# UART_Comm_Isolation.net
KiCad netlist of a schematic drawn in Altium Designer
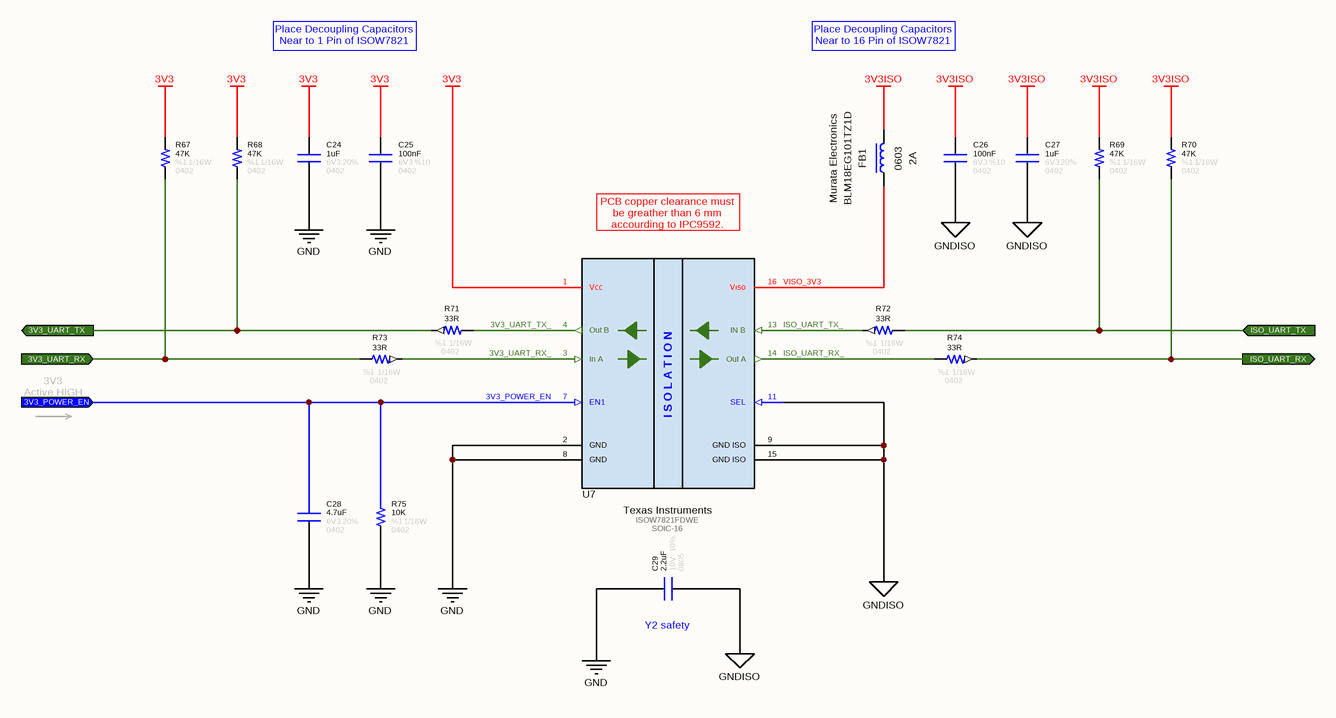
[diagram p0: UART Comm Isolation.SchDoc]

(export (version "E")
  (design (tool "Eeschema 10.0.6"))
  (components
    (comp (ref "C24")
      (value "1uF")
      (footprint "CAPACITOR_0402")
      (description "Capacitor (MLCC) - 1uF / 6V3 / 0402")
      (fields
        (field (name "MANUFACTURER PART NUMBER") "GRM153R60J105ME95D")
        (field (name "TOLERANCE") "20%")
        (field (name "CASE") "0402")
        (field (name "VOLTAGE") "6V3")
        (field (name "Comment") "Capacitor - 1uF [0402] (MLCC)")
      )
      (libsource (lib "Akkoyun") (part "Capacitor - 1uF [0402-6V3]"))
    )
    (comp (ref "C25")
      (value "100nF")
      (footprint "CAPACITOR_0402")
      (description "Capacitor - 100nF [0402-6V3] (Ceramic)")
      (fields
        (field (name "MANUFACTURER PART NUMBER") "04026D104KAT4A")
        (field (name "TOLERANCE") "%10")
        (field (name "VOLTAGE") "6V3")
        (field (name "CASE") "0402")
        (field (name "Comment") "Capacitor - 100nF [0402] (Ceramic)")
      )
      (libsource (lib "Akkoyun") (part "Capacitor - 100nF [0402-6V3]"))
    )
    (comp (ref "C26")
      (value "100nF")
      (footprint "CAPACITOR_0402")
      (description "Capacitor - 100nF [0402-6V3] (Ceramic)")
      (fields
        (field (name "MANUFACTURER PART NUMBER") "04026D104KAT4A")
        (field (name "TOLERANCE") "%10")
        (field (name "VOLTAGE") "6V3")
        (field (name "CASE") "0402")
        (field (name "Comment") "Capacitor - 100nF [0402] (Ceramic)")
      )
      (libsource (lib "Akkoyun") (part "Capacitor - 100nF [0402-6V3]"))
    )
    (comp (ref "C27")
      (value "1uF")
      (footprint "CAPACITOR_0402")
      (description "Capacitor (MLCC) - 1uF / 6V3 / 0402")
      (fields
        (field (name "MANUFACTURER PART NUMBER") "GRM153R60J105ME95D")
        (field (name "TOLERANCE") "20%")
        (field (name "CASE") "0402")
        (field (name "VOLTAGE") "6V3")
        (field (name "Comment") "Capacitor - 1uF [0402] (MLCC)")
      )
      (libsource (lib "Akkoyun") (part "Capacitor - 1uF [0402-6V3]"))
    )
    (comp (ref "C28")
      (value "4.7uF")
      (footprint "CAPACITOR_0402")
      (description "Multilayer Ceramic Capacitors - SMD - 6V3 4.7uF X5R 0402 20%")
      (fields
        (field (name "MANUFACTURER PART NUMBER") "C0402C475M9PACTU")
        (field (name "TOLERANCE") "20%")
        (field (name "CASE") "0402")
        (field (name "VOLTAGE") "6V3")
        (field (name "Comment") "Capacitor - 4.7uF [0402] (Ceramic)")
      )
      (libsource (lib "Akkoyun") (part "Capacitor - 4.7uF [0402-6V3]"))
    )
    (comp (ref "C29")
      (value "2.2uF")
      (footprint "CAPACITOR_0805")
      (description "Multilayer Ceramic Capacitors MLCC - SMD/SMT WCAP-CSGP 2.2uF 0805 10% 10V MLCC")
      (fields
        (field (name "MANUFACTURER PART NUMBER") "885012207024")
        (field (name "TOLERANCE") "10%")
        (field (name "CASE") "0805")
        (field (name "VOLTAGE") "10V")
        (field (name "Comment") "Capacitor - 2.2uF [0805] (MLCC)")
      )
      (libsource (lib "Akkoyun") (part "Capacitor - 2.2uF [0805-10V]"))
    )
    (comp (ref "FB1")
      (value "Ferrite Bead")
      (footprint "INDUCTOR_0603")
      (description "Ferrite Beads 0603 100ohms 2000mA Auto Infotainment")
      (fields
        (field (name "TOLERANCE") "25%")
        (field (name "MAXIMUM DC CURRENT") "2A")
        (field (name "CASE") "0603")
        (field (name "MANUFACTURER PART NUMBER") "BLM18EG101TZ1D")
        (field (name "MANUFACTURER NAME") "Murata Electronics")
      )
      (libsource (lib "Akkoyun") (part "Inductor - Ferrite Bead [SMD]"))
    )
    (comp (ref "R67")
      (value "47K")
      (footprint "RESISTOR_0402")
      (description "Thick Film Resistors - SMD 1/16 W 47 KOhm 1%")
      (fields
        (field (name "MANUFACTURER PART NUMBER") "CRCW040247K0FKED")
        (field (name "TOLERANCE") "%1")
        (field (name "CASE") "0402")
        (field (name "POWER") "1/16W")
        (field (name "Comment") "47K - 0402 - %1 - 1/16W")
      )
      (libsource (lib "Akkoyun") (part "Resistor - 47K [0402]"))
    )
    (comp (ref "R68")
      (value "47K")
      (footprint "RESISTOR_0402")
      (description "Thick Film Resistors - SMD 1/16 W 47 KOhm 1%")
      (fields
        (field (name "MANUFACTURER PART NUMBER") "CRCW040247K0FKED")
        (field (name "TOLERANCE") "%1")
        (field (name "CASE") "0402")
        (field (name "POWER") "1/16W")
        (field (name "Comment") "47K - 0402 - %1 - 1/16W")
      )
      (libsource (lib "Akkoyun") (part "Resistor - 47K [0402]"))
    )
    (comp (ref "R69")
      (value "47K")
      (footprint "RESISTOR_0402")
      (description "Thick Film Resistors - SMD 1/16 W 47 KOhm 1%")
      (fields
        (field (name "MANUFACTURER PART NUMBER") "CRCW040247K0FKED")
        (field (name "TOLERANCE") "%1")
        (field (name "CASE") "0402")
        (field (name "POWER") "1/16W")
        (field (name "Comment") "47K - 0402 - %1 - 1/16W")
      )
      (libsource (lib "Akkoyun") (part "Resistor - 47K [0402]"))
    )
    (comp (ref "R70")
      (value "47K")
      (footprint "RESISTOR_0402")
      (description "Thick Film Resistors - SMD 1/16 W 47 KOhm 1%")
      (fields
        (field (name "MANUFACTURER PART NUMBER") "CRCW040247K0FKED")
        (field (name "TOLERANCE") "%1")
        (field (name "CASE") "0402")
        (field (name "POWER") "1/16W")
        (field (name "Comment") "47K - 0402 - %1 - 1/16W")
      )
      (libsource (lib "Akkoyun") (part "Resistor - 47K [0402]"))
    )
    (comp (ref "R71")
      (value "33R")
      (footprint "RESISTOR_0402")
      (description "Thick Film Resistors - SMD 1/16 W 33 Ohm 1%")
      (fields
        (field (name "MANUFACTURER PART NUMBER") "CRCW040233R0FKED")
        (field (name "CASE") "0402")
        (field (name "TOLERANCE") "%1")
        (field (name "POWER") "1/16W")
        (field (name "Comment") "33R - 0402 - %1 - 1/16W")
      )
      (libsource (lib "Akkoyun") (part "Resistor - 33R [0402]"))
    )
    (comp (ref "R72")
      (value "33R")
      (footprint "RESISTOR_0402")
      (description "Thick Film Resistors - SMD 1/16 W 33 Ohm 1%")
      (fields
        (field (name "MANUFACTURER PART NUMBER") "CRCW040233R0FKED")
        (field (name "CASE") "0402")
        (field (name "TOLERANCE") "%1")
        (field (name "POWER") "1/16W")
        (field (name "Comment") "33R - 0402 - %1 - 1/16W")
      )
      (libsource (lib "Akkoyun") (part "Resistor - 33R [0402]"))
    )
    (comp (ref "R73")
      (value "33R")
      (footprint "RESISTOR_0402")
      (description "Thick Film Resistors - SMD 1/16 W 33 Ohm 1%")
      (fields
        (field (name "MANUFACTURER PART NUMBER") "CRCW040233R0FKED")
        (field (name "CASE") "0402")
        (field (name "TOLERANCE") "%1")
        (field (name "POWER") "1/16W")
        (field (name "Comment") "33R - 0402 - %1 - 1/16W")
      )
      (libsource (lib "Akkoyun") (part "Resistor - 33R [0402]"))
    )
    (comp (ref "R74")
      (value "33R")
      (footprint "RESISTOR_0402")
      (description "Thick Film Resistors - SMD 1/16 W 33 Ohm 1%")
      (fields
        (field (name "MANUFACTURER PART NUMBER") "CRCW040233R0FKED")
        (field (name "CASE") "0402")
        (field (name "TOLERANCE") "%1")
        (field (name "POWER") "1/16W")
        (field (name "Comment") "33R - 0402 - %1 - 1/16W")
      )
      (libsource (lib "Akkoyun") (part "Resistor - 33R [0402]"))
    )
    (comp (ref "R75")
      (value "10K")
      (footprint "RESISTOR_0402")
      (description "Thick Film Resistors - SMD 1/16 W 10 KOhm 1%")
      (fields
        (field (name "MANUFACTURER PART NUMBER") "CRCW040210K0FKED")
        (field (name "TOLERANCE") "%1")
        (field (name "CASE") "0402")
        (field (name "POWER") "1/16W")
        (field (name "Comment") "10K - 0402 - %1 - 1/16W")
      )
      (libsource (lib "Akkoyun") (part "Resistor - 10K [0402]"))
    )
    (comp (ref "U7")
      (value "ISOW7821")
      (footprint "SOIC-16 DW")
      (description "Digital Isolators Dual-channel 1/1 r einforced digital is A 595-ISOW7821FDWER")
      (fields
        (field (name "MANUFACTURER NAME") "Texas Instruments")
        (field (name "MANUFACTURER PART NUMBER") "ISOW7821FDWE")
        (field (name "CASE") "SOIC-16")
      )
      (libsource (lib "Akkoyun") (part "IC - ISOW7821"))
    )
  )
  (nets
    (net (code "1") (name "/3V3_POWER_EN") (class "Default")
      (node (ref "C28") (pin "2") (pinfunction "2_2") (pintype "passive"))
      (node (ref "R75") (pin "2") (pinfunction "2_2") (pintype "passive"))
      (node (ref "U7") (pin "7") (pinfunction "EN1_7") (pintype "input"))
    )
    (net (code "2") (name "/3V3_UART_RX") (class "Default")
      (node (ref "R67") (pin "1") (pinfunction "1_1") (pintype "passive"))
      (node (ref "R73") (pin "2") (pinfunction "2_2") (pintype "output"))
    )
    (net (code "3") (name "/3V3_UART_RX_") (class "Default")
      (node (ref "R73") (pin "1") (pinfunction "1_1") (pintype "passive"))
      (node (ref "U7") (pin "3") (pinfunction "In_A_3") (pintype "input"))
    )
    (net (code "4") (name "/3V3_UART_TX") (class "Default")
      (node (ref "R68") (pin "1") (pinfunction "1_1") (pintype "passive"))
      (node (ref "R71") (pin "2") (pinfunction "2_2") (pintype "output"))
    )
    (net (code "5") (name "/3V3_UART_TX_") (class "Default")
      (node (ref "R71") (pin "1") (pinfunction "1_1") (pintype "passive"))
      (node (ref "U7") (pin "4") (pinfunction "Out_B_4") (pintype "output"))
    )
    (net (code "6") (name "/ISO_UART_RX") (class "Default")
      (node (ref "R70") (pin "1") (pinfunction "1_1") (pintype "passive"))
      (node (ref "R74") (pin "1") (pinfunction "1_1") (pintype "passive"))
    )
    (net (code "7") (name "/ISO_UART_RX_") (class "Default")
      (node (ref "R74") (pin "2") (pinfunction "2_2") (pintype "output"))
      (node (ref "U7") (pin "14") (pinfunction "Out_A_14") (pintype "output"))
    )
    (net (code "8") (name "/ISO_UART_TX") (class "Default")
      (node (ref "R69") (pin "1") (pinfunction "1_1") (pintype "passive"))
      (node (ref "R72") (pin "1") (pinfunction "1_1") (pintype "passive"))
    )
    (net (code "9") (name "/ISO_UART_TX_") (class "Default")
      (node (ref "R72") (pin "2") (pinfunction "2_2") (pintype "output"))
      (node (ref "U7") (pin "13") (pinfunction "IN_B_13") (pintype "input"))
    )
    (net (code "10") (name "/VISO_3V3") (class "Default")
      (node (ref "FB1") (pin "1") (pinfunction "1_1") (pintype "passive"))
      (node (ref "U7") (pin "16") (pinfunction "Viso_16") (pintype "power_in"))
    )
    (net (code "11") (name "3V3") (class "Default")
      (node (ref "C24") (pin "2") (pinfunction "2_2") (pintype "passive"))
      (node (ref "C25") (pin "2") (pinfunction "2_2") (pintype "passive"))
      (node (ref "R67") (pin "2") (pinfunction "2_2") (pintype "passive"))
      (node (ref "R68") (pin "2") (pinfunction "2_2") (pintype "passive"))
      (node (ref "U7") (pin "1") (pinfunction "Vcc_1") (pintype "power_in"))
    )
    (net (code "12") (name "3V3ISO") (class "Default")
      (node (ref "C26") (pin "2") (pinfunction "2_2") (pintype "passive"))
      (node (ref "C27") (pin "2") (pinfunction "2_2") (pintype "passive"))
      (node (ref "FB1") (pin "2") (pinfunction "2_2") (pintype "passive"))
      (node (ref "R69") (pin "2") (pinfunction "2_2") (pintype "passive"))
      (node (ref "R70") (pin "2") (pinfunction "2_2") (pintype "passive"))
    )
    (net (code "13") (name "GND") (class "Default")
      (node (ref "C24") (pin "1") (pinfunction "1_1") (pintype "passive"))
      (node (ref "C25") (pin "1") (pinfunction "1_1") (pintype "passive"))
      (node (ref "C28") (pin "1") (pinfunction "1_1") (pintype "passive"))
      (node (ref "C29") (pin "2") (pinfunction "2_2") (pintype "passive"))
      (node (ref "R75") (pin "1") (pinfunction "1_1") (pintype "passive"))
      (node (ref "U7") (pin "2") (pinfunction "GND_2") (pintype "power_in"))
      (node (ref "U7") (pin "8") (pinfunction "GND_8") (pintype "power_in"))
    )
    (net (code "14") (name "GNDISO") (class "Default")
      (node (ref "C26") (pin "1") (pinfunction "1_1") (pintype "passive"))
      (node (ref "C27") (pin "1") (pinfunction "1_1") (pintype "passive"))
      (node (ref "C29") (pin "1") (pinfunction "1_1") (pintype "passive"))
      (node (ref "U7") (pin "11") (pinfunction "SEL_11") (pintype "input"))
      (node (ref "U7") (pin "15") (pinfunction "GND_ISO_15") (pintype "power_in"))
      (node (ref "U7") (pin "9") (pinfunction "GND_ISO_9") (pintype "power_in"))
    )
    (net (code "15") (name "unconnected-(U7-NC-Pad5)") (class "Default")
      (node (ref "U7") (pin "5") (pinfunction "NC_5") (pintype "passive"))
    )
    (net (code "16") (name "unconnected-(U7-NC-Pad6)") (class "Default")
      (node (ref "U7") (pin "6") (pinfunction "NC_6") (pintype "passive"))
    )
    (net (code "17") (name "unconnected-(U7-NC-Pad10)") (class "Default")
      (node (ref "U7") (pin "10") (pinfunction "NC_10") (pintype "passive"))
    )
    (net (code "18") (name "unconnected-(U7-NC-Pad12)") (class "Default")
      (node (ref "U7") (pin "12") (pinfunction "NC_12") (pintype "passive"))
    )
  )
)
